# Sheet1.net
KiCad netlist of a schematic drawn in Altium Designer
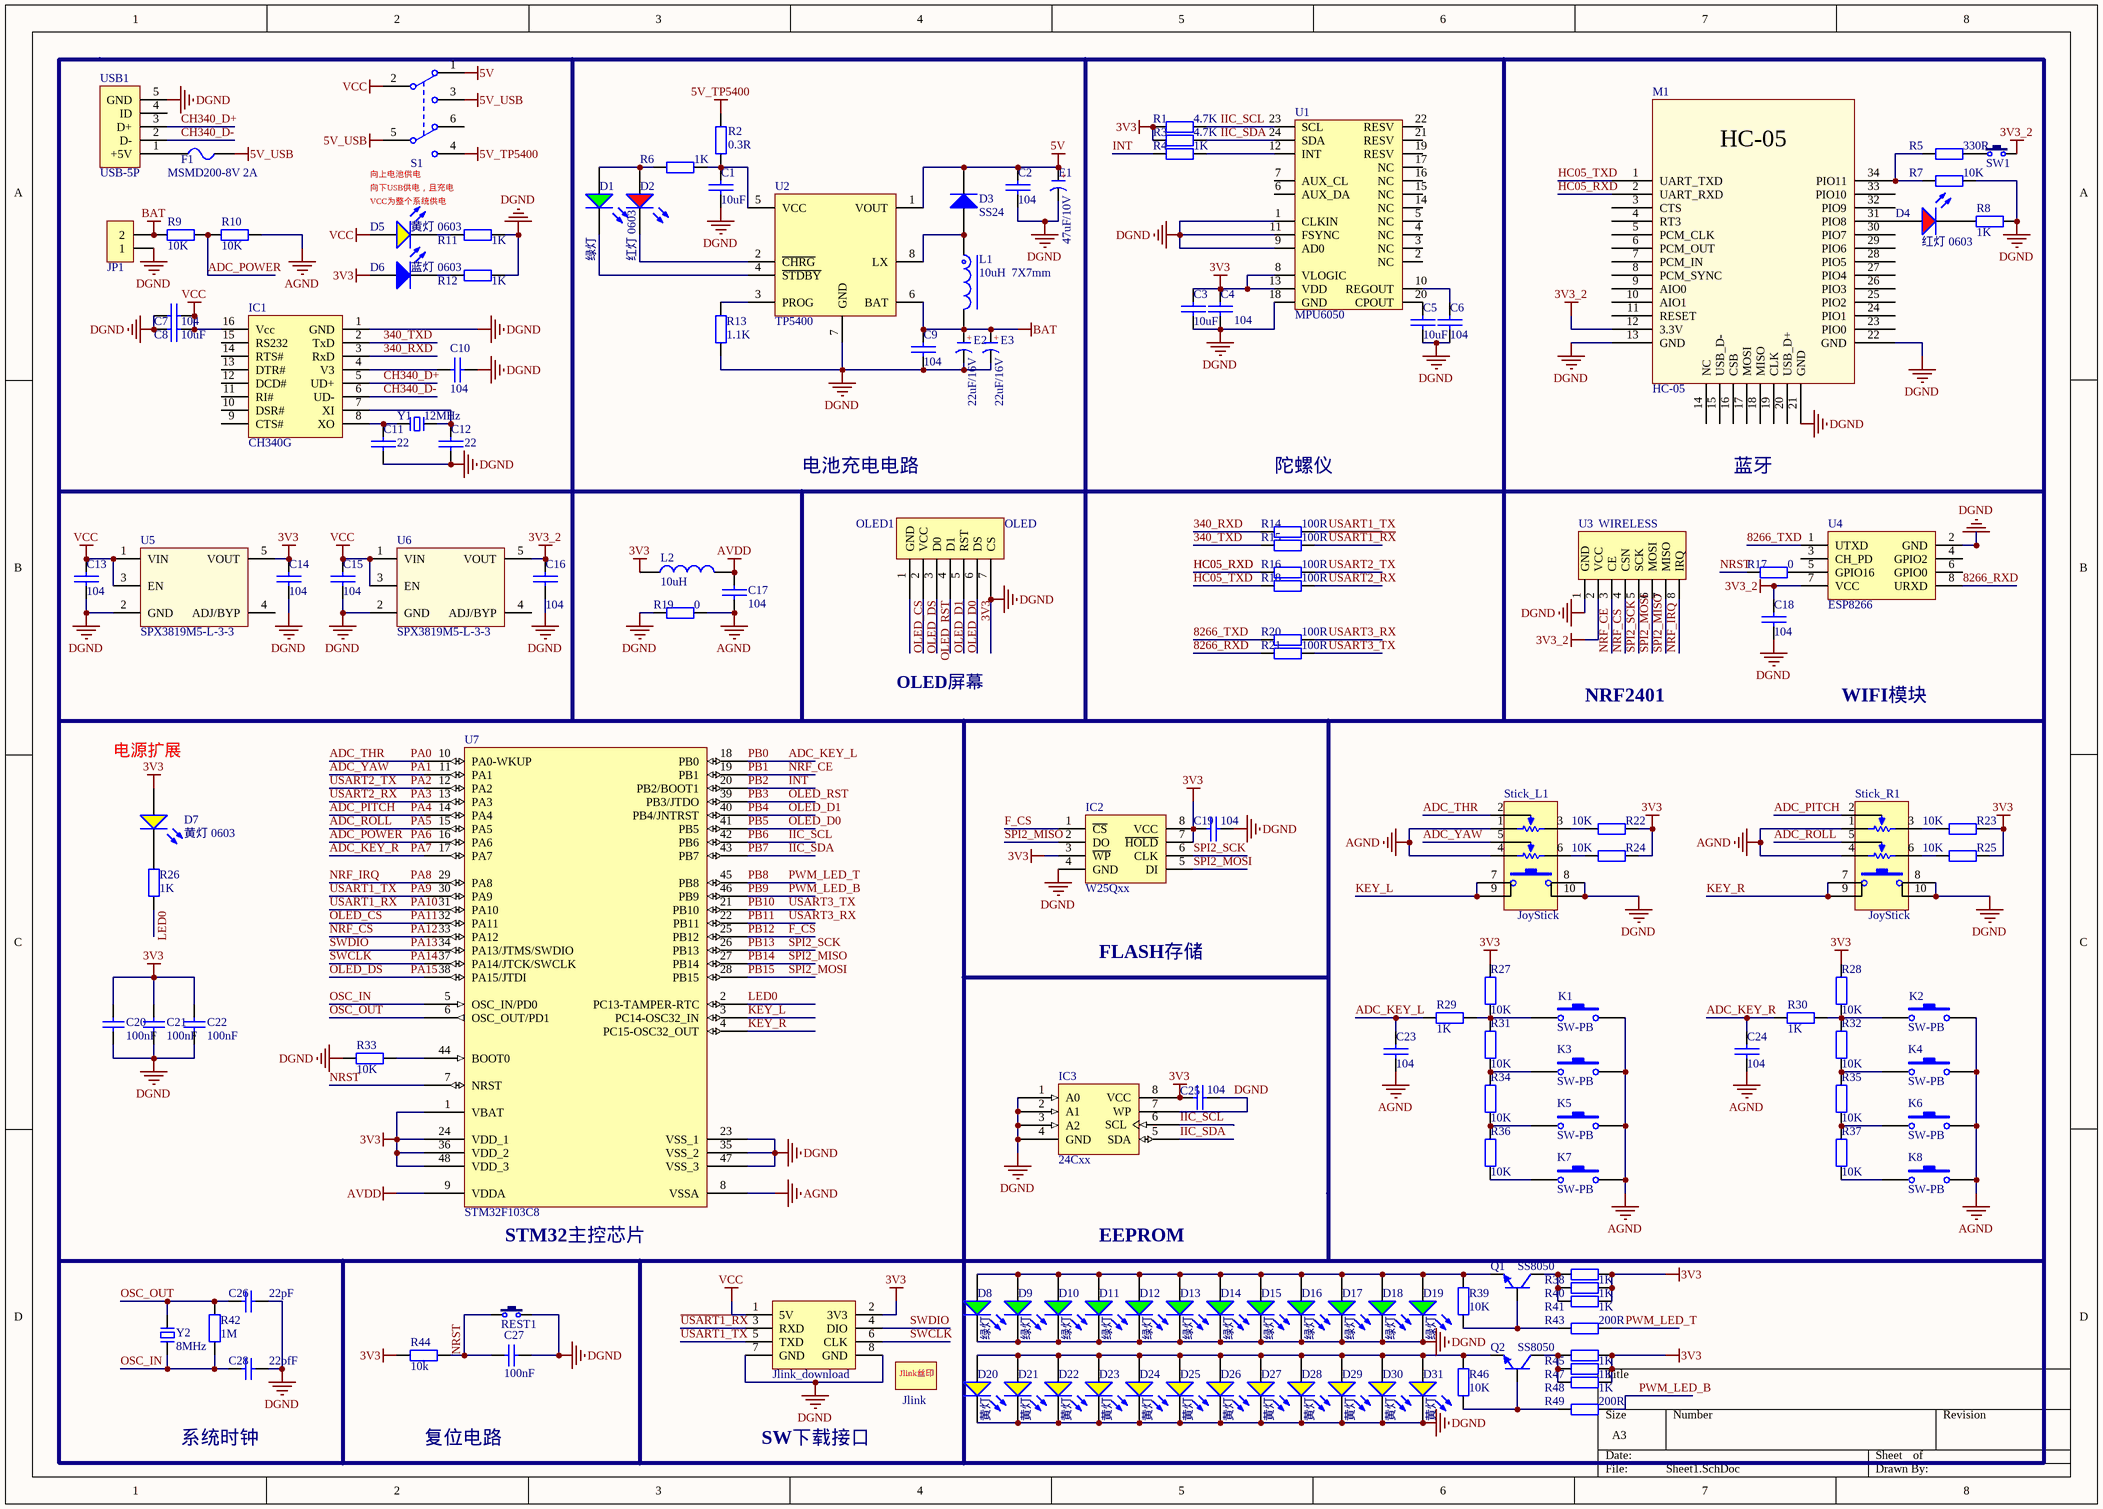
[diagram p0: Sheet1.SchDoc]

(export (version "E")
  (design (tool "Eeschema 10.0.6"))
  (components
    (comp (ref "*1")
      (value "Jlink_download")
      (footprint "HDR2.54-M-LI-2x4P")
      (description "Jlink下载器")
      (libsource (lib "15.1 - 未分类器件") (part "Jlink_下载器"))
    )
    (comp (ref "*2")
      (value "Jlink")
      (footprint "Jlink_Load")
      (description "Jlink丝印")
      (libsource (lib "15.1 - 未分类器件") (part "Jlink"))
    )
    (comp (ref "C1")
      (value "10uF")
      (footprint "LC-0805_C")
      (description "Capacitor 0805")
      (libsource (lib "CD's_LIB_2018") (part "0805C"))
    )
    (comp (ref "C2")
      (value "104")
      (footprint "LC-0603_C")
      (description "Capacitor 0805")
      (libsource (lib "CD's_LIB_2018") (part "0805C"))
    )
    (comp (ref "C3")
      (value "10uF")
      (footprint "LC-0805_C")
      (description "Capacitor 0805")
      (libsource (lib "CD's_LIB_2018") (part "0805C"))
    )
    (comp (ref "C4")
      (value "104")
      (footprint "LC-0603_C")
      (description "Capacitor 0805")
      (libsource (lib "CD's_LIB_2018") (part "0805C"))
    )
    (comp (ref "C5")
      (value "10uF")
      (footprint "LC-0805_C")
      (description "Capacitor 0805")
      (libsource (lib "CD's_LIB_2018") (part "0805C"))
    )
    (comp (ref "C6")
      (value "104")
      (footprint "LC-0603_C")
      (description "Capacitor 0805")
      (libsource (lib "CD's_LIB_2018") (part "0805C"))
    )
    (comp (ref "C7")
      (value "104")
      (footprint "LC-0603_C")
      (description "Capacitor 0805")
      (libsource (lib "CD's_LIB_2018") (part "0805C"))
    )
    (comp (ref "C8")
      (value "10uF")
      (footprint "LC-0805_C")
      (description "Capacitor 0805")
      (libsource (lib "CD's_LIB_2018") (part "0805C"))
    )
    (comp (ref "C9")
      (value "104")
      (footprint "LC-0603_C")
      (description "Capacitor 0805")
      (libsource (lib "CD's_LIB_2018") (part "0805C"))
    )
    (comp (ref "C10")
      (value "104")
      (footprint "LC-0603_C")
      (description "Capacitor 0805")
      (libsource (lib "CD's_LIB_2018") (part "0805C"))
    )
    (comp (ref "C11")
      (value "22")
      (footprint "LC-0603_C")
      (description "Capacitor 0805")
      (libsource (lib "CD's_LIB_2018") (part "0805C"))
    )
    (comp (ref "C12")
      (value "22")
      (footprint "LC-0603_C")
      (description "Capacitor 0805")
      (libsource (lib "CD's_LIB_2018") (part "0805C"))
    )
    (comp (ref "C13")
      (value "104")
      (footprint "LC-0603_C")
      (description "Capacitor 0805")
      (libsource (lib "CD's_LIB_2018") (part "0805C"))
    )
    (comp (ref "C14")
      (value "104")
      (footprint "LC-0603_C")
      (description "Capacitor 0805")
      (libsource (lib "CD's_LIB_2018") (part "0805C"))
    )
    (comp (ref "C15")
      (value "104")
      (footprint "LC-0603_C")
      (description "Capacitor 0805")
      (libsource (lib "CD's_LIB_2018") (part "0805C"))
    )
    (comp (ref "C16")
      (value "104")
      (footprint "LC-0603_C")
      (description "Capacitor 0805")
      (libsource (lib "CD's_LIB_2018") (part "0805C"))
    )
    (comp (ref "C17")
      (value "104")
      (footprint "LC-0603_C")
      (description "Capacitor 0805")
      (libsource (lib "CD's_LIB_2018") (part "0805C"))
    )
    (comp (ref "C18")
      (value "104")
      (footprint "LC-0603_C")
      (description "Capacitor 0805")
      (libsource (lib "CD's_LIB_2018") (part "0805C"))
    )
    (comp (ref "C19")
      (value "104")
      (footprint "LC-0603_C")
      (description "Capacitor 0805")
      (libsource (lib "CD's_LIB_2018") (part "0805C"))
    )
    (comp (ref "C20")
      (value "100nF")
      (footprint "LC-0603_C")
      (description "无极性电容")
      (fields (field (name "PUBLISHER") "Altium Limited"))
      (libsource (lib "liu_2016") (part "Cap"))
    )
    (comp (ref "C21")
      (value "100nF")
      (footprint "LC-0603_C")
      (description "无极性电容")
      (fields (field (name "PUBLISHER") "Altium Limited"))
      (libsource (lib "liu_2016") (part "Cap"))
    )
    (comp (ref "C22")
      (value "100nF")
      (footprint "LC-0603_C")
      (description "无极性电容")
      (fields (field (name "PUBLISHER") "Altium Limited"))
      (libsource (lib "liu_2016") (part "Cap"))
    )
    (comp (ref "C23")
      (value "104")
      (footprint "LC-0603_C")
      (description "Capacitor 0805")
      (libsource (lib "CD's_LIB_2018") (part "0805C"))
    )
    (comp (ref "C24")
      (value "104")
      (footprint "LC-0603_C")
      (description "Capacitor 0805")
      (libsource (lib "CD's_LIB_2018") (part "0805C"))
    )
    (comp (ref "C25")
      (value "104")
      (footprint "LC-0603_C")
      (description "Capacitor 0805")
      (libsource (lib "CD's_LIB_2018") (part "0805C"))
    )
    (comp (ref "C26")
      (value "22pF")
      (footprint "LC-0603_C")
      (description "无极性电容")
      (fields (field (name "PUBLISHER") "Altium Limited"))
      (libsource (lib "liu_2016") (part "Cap"))
    )
    (comp (ref "C27")
      (value "100nF")
      (footprint "LC-0603_C")
      (description "无极性电容")
      (fields (field (name "PUBLISHER") "Altium Limited"))
      (libsource (lib "liu_2016") (part "Cap"))
    )
    (comp (ref "C28")
      (value "22pfF")
      (footprint "LC-0603_C")
      (description "无极性电容")
      (fields (field (name "PUBLISHER") "Altium Limited"))
      (libsource (lib "liu_2016") (part "Cap"))
    )
    (comp (ref "D1")
      (value "绿灯")
      (footprint "LC-0603_LED_S1")
      (description "发光二极管")
      (libsource (lib "Miscellaneous Devices LC") (part "绿灯"))
    )
    (comp (ref "D2")
      (value "红灯 0603")
      (footprint "LC-0603_LED_S1")
      (description "发光二极管")
      (libsource (lib "Miscellaneous Devices LC") (part "0603 红灯"))
    )
    (comp (ref "D3")
      (value "SS24")
      (footprint "SMB")
      (description "High Conductance Fast Diode")
      (fields (field (name "PUBLISHER") "Altium Limited"))
      (libsource (lib "Miscellaneous Devices") (part "Diode 1N4148"))
    )
    (comp (ref "D4")
      (value "红灯 0603")
      (footprint "LC-0603_LED_S1")
      (description "发光二极管")
      (libsource (lib "Miscellaneous Devices LC") (part "0603 红灯"))
    )
    (comp (ref "D5")
      (value "黄灯 0603")
      (footprint "LC-0603_LED_S1")
      (description "发光二极管")
      (libsource (lib "Miscellaneous Devices LC") (part "0603 黄灯"))
    )
    (comp (ref "D6")
      (value "蓝灯 0603")
      (footprint "LC-0603_LED_S1")
      (description "发光二极管")
      (libsource (lib "Miscellaneous Devices LC") (part "0603 蓝灯"))
    )
    (comp (ref "D7")
      (value "黄灯 0603")
      (footprint "LC-0603_LED_S1")
      (description "发光二极管")
      (libsource (lib "Miscellaneous Devices LC") (part "0603 黄灯"))
    )
    (comp (ref "D8")
      (value "绿灯")
      (footprint "LC-0603_LED_S1")
      (description "发光二极管")
      (libsource (lib "Miscellaneous Devices LC") (part "绿灯"))
    )
    (comp (ref "D9")
      (value "绿灯")
      (footprint "LC-0603_LED_S1")
      (description "发光二极管")
      (libsource (lib "Miscellaneous Devices LC") (part "绿灯"))
    )
    (comp (ref "D10")
      (value "绿灯")
      (footprint "LC-0603_LED_S1")
      (description "发光二极管")
      (libsource (lib "Miscellaneous Devices LC") (part "绿灯"))
    )
    (comp (ref "D11")
      (value "绿灯")
      (footprint "LC-0603_LED_S1")
      (description "发光二极管")
      (libsource (lib "Miscellaneous Devices LC") (part "绿灯"))
    )
    (comp (ref "D12")
      (value "绿灯")
      (footprint "LC-0603_LED_S1")
      (description "发光二极管")
      (libsource (lib "Miscellaneous Devices LC") (part "绿灯"))
    )
    (comp (ref "D13")
      (value "绿灯")
      (footprint "LC-0603_LED_S1")
      (description "发光二极管")
      (libsource (lib "Miscellaneous Devices LC") (part "绿灯"))
    )
    (comp (ref "D14")
      (value "绿灯")
      (footprint "LC-0603_LED_S1")
      (description "发光二极管")
      (libsource (lib "Miscellaneous Devices LC") (part "绿灯"))
    )
    (comp (ref "D15")
      (value "绿灯")
      (footprint "LC-0603_LED_S1")
      (description "发光二极管")
      (libsource (lib "Miscellaneous Devices LC") (part "绿灯"))
    )
    (comp (ref "D16")
      (value "绿灯")
      (footprint "LC-0603_LED_S1")
      (description "发光二极管")
      (libsource (lib "Miscellaneous Devices LC") (part "绿灯"))
    )
    (comp (ref "D17")
      (value "绿灯")
      (footprint "LC-0603_LED_S1")
      (description "发光二极管")
      (libsource (lib "Miscellaneous Devices LC") (part "绿灯"))
    )
    (comp (ref "D18")
      (value "绿灯")
      (footprint "LC-0603_LED_S1")
      (description "发光二极管")
      (libsource (lib "Miscellaneous Devices LC") (part "绿灯"))
    )
    (comp (ref "D19")
      (value "绿灯")
      (footprint "LC-0603_LED_S1")
      (description "发光二极管")
      (libsource (lib "Miscellaneous Devices LC") (part "绿灯"))
    )
    (comp (ref "D20")
      (value "黄灯")
      (footprint "LC-0603_LED_S1")
      (description "发光二极管")
      (libsource (lib "Miscellaneous Devices LC") (part "0603 黄灯"))
    )
    (comp (ref "D21")
      (value "黄灯")
      (footprint "LC-0603_LED_S1")
      (description "发光二极管")
      (libsource (lib "Miscellaneous Devices LC") (part "0603 黄灯"))
    )
    (comp (ref "D22")
      (value "黄灯")
      (footprint "LC-0603_LED_S1")
      (description "发光二极管")
      (libsource (lib "Miscellaneous Devices LC") (part "0603 黄灯"))
    )
    (comp (ref "D23")
      (value "黄灯")
      (footprint "LC-0603_LED_S1")
      (description "发光二极管")
      (libsource (lib "Miscellaneous Devices LC") (part "0603 黄灯"))
    )
    (comp (ref "D24")
      (value "黄灯")
      (footprint "LC-0603_LED_S1")
      (description "发光二极管")
      (libsource (lib "Miscellaneous Devices LC") (part "0603 黄灯"))
    )
    (comp (ref "D25")
      (value "黄灯")
      (footprint "LC-0603_LED_S1")
      (description "发光二极管")
      (libsource (lib "Miscellaneous Devices LC") (part "0603 黄灯"))
    )
    (comp (ref "D26")
      (value "黄灯")
      (footprint "LC-0603_LED_S1")
      (description "发光二极管")
      (libsource (lib "Miscellaneous Devices LC") (part "0603 黄灯"))
    )
    (comp (ref "D27")
      (value "黄灯")
      (footprint "LC-0603_LED_S1")
      (description "发光二极管")
      (libsource (lib "Miscellaneous Devices LC") (part "0603 黄灯"))
    )
    (comp (ref "D28")
      (value "黄灯")
      (footprint "LC-0603_LED_S1")
      (description "发光二极管")
      (libsource (lib "Miscellaneous Devices LC") (part "0603 黄灯"))
    )
    (comp (ref "D29")
      (value "黄灯")
      (footprint "LC-0603_LED_S1")
      (description "发光二极管")
      (libsource (lib "Miscellaneous Devices LC") (part "0603 黄灯"))
    )
    (comp (ref "D30")
      (value "黄灯")
      (footprint "LC-0603_LED_S1")
      (description "发光二极管")
      (libsource (lib "Miscellaneous Devices LC") (part "0603 黄灯"))
    )
    (comp (ref "D31")
      (value "黄灯")
      (footprint "LC-0603_LED_S1")
      (description "发光二极管")
      (libsource (lib "Miscellaneous Devices LC") (part "0603 黄灯"))
    )
    (comp (ref "E1")
      (value "47uF/10V")
      (footprint "CD B(3528)")
      (description "贴片钽电容")
      (fields (field (name "版权归属") "源创客"))
      (libsource (lib "3.1   - 电阻-电容-电感") (part "C-CD"))
    )
    (comp (ref "E2")
      (value "22uF/16V")
      (footprint "CD B(3528)")
      (description "贴片钽电容")
      (fields (field (name "版权归属") "源创客"))
      (libsource (lib "3.1   - 电阻-电容-电感") (part "C-CD"))
    )
    (comp (ref "E3")
      (value "22uF/16V")
      (footprint "CD B(3528)")
      (description "贴片钽电容")
      (fields (field (name "版权归属") "源创客"))
      (libsource (lib "3.1   - 电阻-电容-电感") (part "C-CD"))
    )
    (comp (ref "F1")
      (value "MSMD200-8V 2A")
      (footprint "FU 0805")
      (description "贴片保险丝")
      (fields (field (name "版权归属") "源创客"))
      (libsource (lib "10.1 - 保险丝-晶振") (part "FU"))
    )
    (comp (ref "IC1")
      (value "CH340G")
      (footprint "SOP16_M")
      (description "串口转USB")
      (fields (field (name "版权归属") "源创客"))
      (libsource (lib "1.1   - IC芯片") (part "CH340G"))
    )
    (comp (ref "IC2")
      (value "W25Qxx")
      (footprint "SOP8W_M")
      (description "外置Flash")
      (fields (field (name "版权归属") "源创客"))
      (libsource (lib "1.1   - IC芯片") (part "W25Qxx"))
    )
    (comp (ref "IC3")
      (value "24Cxx")
      (footprint "SOP8_M")
      (description "外置EEPROM")
      (fields (field (name "版权归属") "源创客"))
      (libsource (lib "1.1   - IC芯片") (part "24Cxx"))
    )
    (comp (ref "JP1")
      (value "HDR-1X2")
      (footprint "XH2.54-WI-2P")
      (description "2P接插件")
      (fields (field (name "版权归属") "源创客"))
      (libsource (lib "4.5   - 接插件-脚距2.54") (part "Header 2"))
    )
    (comp (ref "K1")
      (value "SW-PB")
      (footprint "TSW DIP-6*6*5")
      (description "Switch")
      (fields (field (name "PUBLISHER") "Altium Limited"))
      (libsource (lib "PCB_Project") (part "SW-PB"))
    )
    (comp (ref "K2")
      (value "SW-PB")
      (footprint "TSW DIP-6*6*5")
      (description "Switch")
      (fields (field (name "PUBLISHER") "Altium Limited"))
      (libsource (lib "PCB_Project") (part "SW-PB"))
    )
    (comp (ref "K3")
      (value "SW-PB")
      (footprint "TSW DIP-6*6*5")
      (description "Switch")
      (fields (field (name "PUBLISHER") "Altium Limited"))
      (libsource (lib "PCB_Project") (part "SW-PB"))
    )
    (comp (ref "K4")
      (value "SW-PB")
      (footprint "TSW DIP-6*6*5")
      (description "Switch")
      (fields (field (name "PUBLISHER") "Altium Limited"))
      (libsource (lib "PCB_Project") (part "SW-PB"))
    )
    (comp (ref "K5")
      (value "SW-PB")
      (footprint "TSW DIP-6*6*5")
      (description "Switch")
      (fields (field (name "PUBLISHER") "Altium Limited"))
      (libsource (lib "PCB_Project") (part "SW-PB"))
    )
    (comp (ref "K6")
      (value "SW-PB")
      (footprint "TSW DIP-6*6*5")
      (description "Switch")
      (fields (field (name "PUBLISHER") "Altium Limited"))
      (libsource (lib "PCB_Project") (part "SW-PB"))
    )
    (comp (ref "K7")
      (value "SW-PB")
      (footprint "TSW DIP-6*6*5")
      (description "Switch")
      (fields (field (name "PUBLISHER") "Altium Limited"))
      (libsource (lib "PCB_Project") (part "SW-PB"))
    )
    (comp (ref "K8")
      (value "SW-PB")
      (footprint "TSW DIP-6*6*5")
      (description "Switch")
      (fields (field (name "PUBLISHER") "Altium Limited"))
      (libsource (lib "PCB_Project") (part "SW-PB"))
    )
    (comp (ref "L1")
      (value "10uH  7X7mm")
      (footprint "CD75")
      (description "贴片功率电感")
      (fields (field (name "版权归属") "源创客"))
      (libsource (lib "3.1   - 电阻-电容-电感") (part "L-CD"))
    )
    (comp (ref "L2")
      (value "10uH")
      (footprint "L 0603")
      (description "小功率贴片电感")
      (fields (field (name "版权归属") "源创客"))
      (libsource (lib "3.1   - 电阻-电容-电感") (part "L"))
    )
    (comp (ref "M1")
      (value "HC-05")
      (footprint "HC-05")
      (description "串口蓝牙模块")
      (fields (field (name "版权归属") "源创客"))
      (libsource (lib "13.1 - 模块") (part "HC-05"))
    )
    (comp (ref "OLED1")
      (value "OLED")
      (footprint "OLED_096")
      (description "OLED屏幕")
      (libsource (lib "liu_2016") (part "OLED_SPI"))
    )
    (comp (ref "Q1")
      (value "SS8050")
      (footprint "SOT23-3L")
      (description "高频放大-NPN型")
      (fields (field (name "版权归属") "源创客"))
      (libsource (lib "6.2   - 三极管") (part "8050-SMD"))
    )
    (comp (ref "Q2")
      (value "SS8050")
      (footprint "SOT23-3L")
      (description "高频放大-NPN型")
      (fields (field (name "版权归属") "源创客"))
      (libsource (lib "6.2   - 三极管") (part "8050-SMD"))
    )
    (comp (ref "R1")
      (value "4.7K")
      (footprint "LC-0603_R")
      (description "贴片电阻")
      (fields (field (name "PUBLISHER") "Altium Limited"))
      (libsource (lib "liu_2016") (part "Res1"))
    )
    (comp (ref "R2")
      (value "0.3R")
      (footprint "R 2010_M")
      (description "贴片电阻")
      (fields (field (name "版权归属") "源创客"))
      (libsource (lib "3.1   - 电阻-电容-电感") (part "R"))
    )
    (comp (ref "R3")
      (value "4.7K")
      (footprint "LC-0603_R")
      (description "贴片电阻")
      (fields (field (name "PUBLISHER") "Altium Limited"))
      (libsource (lib "liu_2016") (part "Res1"))
    )
    (comp (ref "R4")
      (value "1K")
      (footprint "LC-0603_R")
      (description "贴片电阻")
      (fields (field (name "PUBLISHER") "Altium Limited"))
      (libsource (lib "liu_2016") (part "Res1"))
    )
    (comp (ref "R5")
      (value "330R")
      (footprint "LC-0603_R")
      (description "贴片电阻")
      (fields (field (name "PUBLISHER") "Altium Limited"))
      (libsource (lib "") (part "Res1_2"))
    )
    (comp (ref "R6")
      (value "1K")
      (footprint "LC-0603_R")
      (description "贴片电阻")
      (fields (field (name "PUBLISHER") "Altium Limited"))
      (libsource (lib "liu_2016") (part "Res1"))
    )
    (comp (ref "R7")
      (value "10K")
      (footprint "LC-0603_R")
      (description "贴片电阻")
      (fields (field (name "PUBLISHER") "Altium Limited"))
      (libsource (lib "") (part "Res1_2"))
    )
    (comp (ref "R8")
      (value "1K")
      (footprint "LC-0603_R")
      (description "贴片电阻")
      (fields (field (name "PUBLISHER") "Altium Limited"))
      (libsource (lib "") (part "Res1_2"))
    )
    (comp (ref "R9")
      (value "10K")
      (footprint "LC-0603_R")
      (description "贴片电阻")
      (fields (field (name "PUBLISHER") "Altium Limited"))
      (libsource (lib "liu_2016") (part "Res1"))
    )
    (comp (ref "R10")
      (value "10K")
      (footprint "LC-0603_R")
      (description "贴片电阻")
      (fields (field (name "PUBLISHER") "Altium Limited"))
      (libsource (lib "liu_2016") (part "Res1"))
    )
    (comp (ref "R11")
      (value "1K")
      (footprint "LC-0603_R")
      (description "贴片电阻")
      (fields (field (name "PUBLISHER") "Altium Limited"))
      (libsource (lib "liu_2016") (part "Res1"))
    )
    (comp (ref "R12")
      (value "1K")
      (footprint "LC-0603_R")
      (description "贴片电阻")
      (fields (field (name "PUBLISHER") "Altium Limited"))
      (libsource (lib "liu_2016") (part "Res1"))
    )
    (comp (ref "R13")
      (value "1.1K")
      (footprint "LC-0603_R")
      (description "贴片电阻")
      (fields (field (name "PUBLISHER") "Altium Limited"))
      (libsource (lib "") (part "Res1_1"))
    )
    (comp (ref "R14")
      (value "100R")
      (footprint "LC-0603_R")
      (description "贴片电阻")
      (fields (field (name "PUBLISHER") "Altium Limited"))
      (libsource (lib "liu_2016") (part "Res1"))
    )
    (comp (ref "R15")
      (value "100R")
      (footprint "LC-0603_R")
      (description "贴片电阻")
      (fields (field (name "PUBLISHER") "Altium Limited"))
      (libsource (lib "liu_2016") (part "Res1"))
    )
    (comp (ref "R16")
      (value "100R")
      (footprint "LC-0603_R")
      (description "贴片电阻")
      (fields (field (name "PUBLISHER") "Altium Limited"))
      (libsource (lib "liu_2016") (part "Res1"))
    )
    (comp (ref "R17")
      (value "0")
      (footprint "LC-0603_R")
      (description "贴片电阻")
      (fields (field (name "PUBLISHER") "Altium Limited"))
      (libsource (lib "liu_2016") (part "Res1"))
    )
    (comp (ref "R18")
      (value "100R")
      (footprint "LC-0603_R")
      (description "贴片电阻")
      (fields (field (name "PUBLISHER") "Altium Limited"))
      (libsource (lib "liu_2016") (part "Res1"))
    )
    (comp (ref "R19")
      (value "0")
      (footprint "LC-0603_R")
      (description "贴片电阻")
      (fields (field (name "PUBLISHER") "Altium Limited"))
      (libsource (lib "liu_2016") (part "Res1"))
    )
    (comp (ref "R20")
      (value "100R")
      (footprint "LC-0603_R")
      (description "贴片电阻")
      (fields (field (name "PUBLISHER") "Altium Limited"))
      (libsource (lib "liu_2016") (part "Res1"))
    )
    (comp (ref "R21")
      (value "100R")
      (footprint "LC-0603_R")
      (description "贴片电阻")
      (fields (field (name "PUBLISHER") "Altium Limited"))
      (libsource (lib "liu_2016") (part "Res1"))
    )
    (comp (ref "R22")
      (value "10K")
      (footprint "LC-0603_R")
      (description "贴片电阻")
      (fields (field (name "PUBLISHER") "Altium Limited"))
      (libsource (lib "") (part "Res1_2"))
    )
    (comp (ref "R23")
      (value "10K")
      (footprint "LC-0603_R")
      (description "贴片电阻")
      (fields (field (name "PUBLISHER") "Altium Limited"))
      (libsource (lib "") (part "Res1_2"))
    )
    (comp (ref "R24")
      (value "10K")
      (footprint "LC-0603_R")
      (description "贴片电阻")
      (fields (field (name "PUBLISHER") "Altium Limited"))
      (libsource (lib "") (part "Res1_2"))
    )
    (comp (ref "R25")
      (value "10K")
      (footprint "LC-0603_R")
      (description "贴片电阻")
      (fields (field (name "PUBLISHER") "Altium Limited"))
      (libsource (lib "") (part "Res1_2"))
    )
    (comp (ref "R26")
      (value "1K")
      (footprint "LC-0603_R")
      (description "贴片电阻")
      (fields (field (name "PUBLISHER") "Altium Limited"))
      (libsource (lib "") (part "Res1_1"))
    )
    (comp (ref "R27")
      (value "10K")
      (footprint "LC-0603_R")
      (description "贴片电阻")
      (fields (field (name "PUBLISHER") "Altium Limited"))
      (libsource (lib "") (part "Res1_1"))
    )
    (comp (ref "R28")
      (value "10K")
      (footprint "LC-0603_R")
      (description "贴片电阻")
      (fields (field (name "PUBLISHER") "Altium Limited"))
      (libsource (lib "") (part "Res1_1"))
    )
    (comp (ref "R29")
      (value "1K")
      (footprint "LC-0603_R")
      (description "贴片电阻")
      (fields (field (name "PUBLISHER") "Altium Limited"))
      (libsource (lib "") (part "Res1_2"))
    )
    (comp (ref "R30")
      (value "1K")
      (footprint "LC-0603_R")
      (description "贴片电阻")
      (fields (field (name "PUBLISHER") "Altium Limited"))
      (libsource (lib "") (part "Res1_2"))
    )
    (comp (ref "R31")
      (value "10K")
      (footprint "LC-0603_R")
      (description "贴片电阻")
      (fields (field (name "PUBLISHER") "Altium Limited"))
      (libsource (lib "") (part "Res1_1"))
    )
    (comp (ref "R32")
      (value "10K")
      (footprint "LC-0603_R")
      (description "贴片电阻")
      (fields (field (name "PUBLISHER") "Altium Limited"))
      (libsource (lib "") (part "Res1_1"))
    )
    (comp (ref "R33")
      (value "10K")
      (footprint "LC-0603_R")
      (description "贴片电阻")
      (fields (field (name "PUBLISHER") "Altium Limited"))
      (libsource (lib "liu_2016") (part "Res1"))
    )
    (comp (ref "R34")
      (value "10K")
      (footprint "LC-0603_R")
      (description "贴片电阻")
      (fields (field (name "PUBLISHER") "Altium Limited"))
      (libsource (lib "") (part "Res1_1"))
    )
    (comp (ref "R35")
      (value "10K")
      (footprint "LC-0603_R")
      (description "贴片电阻")
      (fields (field (name "PUBLISHER") "Altium Limited"))
      (libsource (lib "") (part "Res1_1"))
    )
    (comp (ref "R36")
      (value "10K")
      (footprint "LC-0603_R")
      (description "贴片电阻")
      (fields (field (name "PUBLISHER") "Altium Limited"))
      (libsource (lib "") (part "Res1_1"))
    )
    (comp (ref "R37")
      (value "10K")
      (footprint "LC-0603_R")
      (description "贴片电阻")
      (fields (field (name "PUBLISHER") "Altium Limited"))
      (libsource (lib "") (part "Res1_1"))
    )
    (comp (ref "R38")
      (value "1K")
      (footprint "LC-0603_R")
      (description "贴片电阻")
      (fields (field (name "PUBLISHER") "Altium Limited"))
      (libsource (lib "liu_2016") (part "Res1"))
    )
    (comp (ref "R39")
      (value "10K")
      (footprint "LC-0603_R")
      (description "贴片电阻")
      (fields (field (name "PUBLISHER") "Altium Limited"))
      (libsource (lib "") (part "Res1_1"))
    )
    (comp (ref "R40")
      (value "1K")
      (footprint "LC-0603_R")
      (description "贴片电阻")
      (fields (field (name "PUBLISHER") "Altium Limited"))
      (libsource (lib "liu_2016") (part "Res1"))
    )
    (comp (ref "R41")
      (value "1K")
      (footprint "LC-0603_R")
      (description "贴片电阻")
      (fields (field (name "PUBLISHER") "Altium Limited"))
      (libsource (lib "liu_2016") (part "Res1"))
    )
    (comp (ref "R42")
      (value "1M")
      (footprint "LC-0603_R")
      (description "贴片电阻")
      (fields (field (name "PUBLISHER") "Altium Limited"))
      (libsource (lib "") (part "Res1_3"))
    )
    (comp (ref "R43")
      (value "200R")
      (footprint "LC-0603_R")
      (description "贴片电阻")
      (fields (field (name "PUBLISHER") "Altium Limited"))
      (libsource (lib "liu_2016") (part "Res1"))
    )
    (comp (ref "R44")
      (value "10k")
      (footprint "LC-0603_R")
      (description "贴片电阻")
      (fields (field (name "PUBLISHER") "Altium Limited"))
      (libsource (lib "") (part "Res1_2"))
    )
    (comp (ref "R45")
      (value "1K")
      (footprint "LC-0603_R")
      (description "贴片电阻")
      (fields (field (name "PUBLISHER") "Altium Limited"))
      (libsource (lib "liu_2016") (part "Res1"))
    )
    (comp (ref "R46")
      (value "10K")
      (footprint "LC-0603_R")
      (description "贴片电阻")
      (fields (field (name "PUBLISHER") "Altium Limited"))
      (libsource (lib "") (part "Res1_1"))
    )
    (comp (ref "R47")
      (value "1K")
      (footprint "LC-0603_R")
      (description "贴片电阻")
      (fields (field (name "PUBLISHER") "Altium Limited"))
      (libsource (lib "liu_2016") (part "Res1"))
    )
    (comp (ref "R48")
      (value "1K")
      (footprint "LC-0603_R")
      (description "贴片电阻")
      (fields (field (name "PUBLISHER") "Altium Limited"))
      (libsource (lib "liu_2016") (part "Res1"))
    )
    (comp (ref "R49")
      (value "200R")
      (footprint "LC-0603_R")
      (description "贴片电阻")
      (fields (field (name "PUBLISHER") "Altium Limited"))
      (libsource (lib "liu_2016") (part "Res1"))
    )
    (comp (ref "REST1")
      (value "3x6x5")
      (footprint "TSW SMD-3*6*2.5")
      (description "3x6轻触开关")
      (fields (field (name "版权归属") "源创客"))
      (libsource (lib "5.1   - 按键-开关") (part "TSW 3x6"))
    )
    (comp (ref "S1")
      (value "SK-22D02")
      (footprint "SS-22H07-G2")
      (description "2路波动开关")
      (fields (field (name "版权归属") "源创客"))
      (libsource (lib "5.1   - 按键-开关") (part "SSW-2P"))
    )
    (comp (ref "Stick_L1")
      (value "JoyStick")
      (footprint "Stick")
      (description "模拟摇杆")
      (libsource (lib "Fszhang") (part "JoyStick"))
    )
    (comp (ref "Stick_R1")
      (value "JoyStick")
      (footprint "Stick")
      (description "模拟摇杆")
      (libsource (lib "Fszhang") (part "JoyStick"))
    )
    (comp (ref "SW1")
      (value "3x6x5")
      (footprint "TSW SMD-3*6*2.5")
      (description "3x6轻触开关")
      (fields (field (name "版权归属") "源创客"))
      (libsource (lib "5.1   - 按键-开关") (part "TSW 3x6"))
    )
    (comp (ref "U1")
      (value "MPU6050")
      (footprint "QFN24 4x4_M")
      (description "9轴运动处理传感器")
      (libsource (lib "Explorer STM32F407封装库") (part "MPU6050"))
    )
    (comp (ref "U2")
      (value "TP5400")
      (footprint "SOP8_M")
      (description "锂电池充电芯片")
      (libsource (lib "1.3   - 电源类芯片") (part "TP5400"))
    )
    (comp (ref "U3")
      (value "WIRELESS")
      (footprint "2*4HEADER")
      (libsource (lib "SWUST_PanPan") (part "NRF24L01"))
    )
    (comp (ref "U4")
      (value "ESP8266")
      (footprint "2*4HEADER")
      (description "WIFI通信模块")
      (libsource (lib "13.1 - 模块") (part "ESP8266"))
    )
    (comp (ref "U5")
      (value "SPX3819M5-L-3-3")
      (footprint "SOT23-5M")
      (libsource (lib "SWUST_PanPan") (part "SPX3819M5-L-3-3"))
    )
    (comp (ref "U6")
      (value "SPX3819M5-L-3-3")
      (footprint "SOT23-5M")
      (libsource (lib "SWUST_PanPan") (part "SPX3819M5-L-3-3"))
    )
    (comp (ref "U7")
      (value "STM32F103C8")
      (footprint "LQFP48 7X7_M")
      (description "Flaah:64/RAM:20/IO:36")
      (fields (field (name "版权归属") "源创客"))
      (libsource (lib "2.1   - STM32系列单片机") (part "STM32F103C8"))
    )
    (comp (ref "USB1")
      (value "USB-5P")
      (footprint "USB-MICRO_A")
      (description "微型USB母座")
      (fields (field (name "版权归属") "源创客"))
      (libsource (lib "4.1   - 接口类") (part "USB-5P"))
    )
    (comp (ref "Y1")
      (value "12MHz")
      (footprint "OSC HC-49S")
      (description "2脚无源脚晶振")
      (fields (field (name "版权归属") "源创客"))
      (libsource (lib "10.1 - 保险丝-晶振") (part "XTAL-2P"))
    )
    (comp (ref "Y2")
      (value "8MHz")
      (footprint "OSC HC-49S")
      (description "2脚无源脚晶振")
      (fields (field (name "版权归属") "源创客"))
      (libsource (lib "10.1 - 保险丝-晶振") (part "XTAL-2P"))
    )
  )
  (nets
    (net (code "1") (name "/340_RXD") (class "Default")
      (node (ref "IC1") (pin "3") (pinfunction "RxD_3") (pintype "passive"))
      (node (ref "R14") (pin "2") (pinfunction "2_2") (pintype "passive"))
    )
    (net (code "2") (name "/340_TXD") (class "Default")
      (node (ref "IC1") (pin "2") (pinfunction "TxD_2") (pintype "passive"))
      (node (ref "R15") (pin "2") (pinfunction "2_2") (pintype "passive"))
    )
    (net (code "3") (name "/8266_RXD") (class "Default")
      (node (ref "R21") (pin "2") (pinfunction "2_2") (pintype "passive"))
      (node (ref "U4") (pin "8") (pinfunction "URXD_8") (pintype "passive"))
    )
    (net (code "4") (name "/8266_TXD") (class "Default")
      (node (ref "R20") (pin "2") (pinfunction "2_2") (pintype "passive"))
      (node (ref "U4") (pin "1") (pinfunction "UTXD_1") (pintype "passive"))
    )
    (net (code "5") (name "/ADC_KEY_L") (class "Default")
      (node (ref "C23") (pin "2") (pinfunction "2_2") (pintype "passive"))
      (node (ref "R29") (pin "1") (pinfunction "1_1") (pintype "passive"))
      (node (ref "U7") (pin "18") (pinfunction "PB0_18") (pintype "bidirectional"))
    )
    (net (code "6") (name "/ADC_KEY_R") (class "Default")
      (node (ref "C24") (pin "2") (pinfunction "2_2") (pintype "passive"))
      (node (ref "R30") (pin "1") (pinfunction "1_1") (pintype "passive"))
      (node (ref "U7") (pin "17") (pinfunction "PA7_17") (pintype "bidirectional"))
    )
    (net (code "7") (name "/ADC_PITCH") (class "Default")
      (node (ref "Stick_R1") (pin "2") (pinfunction "TAP_2") (pintype "passive"))
      (node (ref "U7") (pin "14") (pinfunction "PA4_14") (pintype "bidirectional"))
    )
    (net (code "8") (name "/ADC_POWER") (class "Default")
      (node (ref "R10") (pin "2") (pinfunction "2_2") (pintype "passive"))
      (node (ref "R9") (pin "1") (pinfunction "1_1") (pintype "passive"))
      (node (ref "U7") (pin "16") (pinfunction "PA6_16") (pintype "bidirectional"))
    )
    (net (code "9") (name "/ADC_ROLL") (class "Default")
      (node (ref "Stick_R1") (pin "5") (pinfunction "TAP_5") (pintype "passive"))
      (node (ref "U7") (pin "15") (pinfunction "PA5_15") (pintype "bidirectional"))
    )
    (net (code "10") (name "/ADC_THR") (class "Default")
      (node (ref "Stick_L1") (pin "2") (pinfunction "TAP_2") (pintype "passive"))
      (node (ref "U7") (pin "10") (pinfunction "PA0-WKUP_10") (pintype "bidirectional"))
    )
    (net (code "11") (name "/ADC_YAW") (class "Default")
      (node (ref "Stick_L1") (pin "5") (pinfunction "TAP_5") (pintype "passive"))
      (node (ref "U7") (pin "11") (pinfunction "PA1_11") (pintype "bidirectional"))
    )
    (net (code "12") (name "/CH340_D+") (class "Default")
      (node (ref "IC1") (pin "5") (pinfunction "UD+_5") (pintype "passive"))
      (node (ref "USB1") (pin "3") (pinfunction "D+_3") (pintype "passive"))
    )
    (net (code "13") (name "/CH340_D-") (class "Default")
      (node (ref "IC1") (pin "6") (pinfunction "UD-_6") (pintype "passive"))
      (node (ref "USB1") (pin "2") (pinfunction "D-_2") (pintype "passive"))
    )
    (net (code "14") (name "/F_CS") (class "Default")
      (node (ref "IC2") (pin "1") (pinfunction "~{CS}_1") (pintype "passive"))
      (node (ref "U7") (pin "25") (pinfunction "PB12_25") (pintype "bidirectional"))
    )
    (net (code "15") (name "/HC05_RXD") (class "Default")
      (node (ref "M1") (pin "2") (pinfunction "UART_RXD_2") (pintype "passive"))
      (node (ref "R16") (pin "2") (pinfunction "2_2") (pintype "passive"))
    )
    (net (code "16") (name "/HC05_TXD") (class "Default")
      (node (ref "M1") (pin "1") (pinfunction "UART_TXD_1") (pintype "passive"))
      (node (ref "R18") (pin "2") (pinfunction "2_2") (pintype "passive"))
    )
    (net (code "17") (name "/IIC_SCL") (class "Default")
      (node (ref "IC3") (pin "6") (pinfunction "SCL_6") (pintype "input"))
      (node (ref "R1") (pin "1") (pinfunction "1_1") (pintype "passive"))
      (node (ref "U1") (pin "23") (pinfunction "SCL_23") (pintype "passive"))
      (node (ref "U7") (pin "42") (pinfunction "PB6_42") (pintype "bidirectional"))
    )
    (net (code "18") (name "/IIC_SDA") (class "Default")
      (node (ref "IC3") (pin "5") (pinfunction "SDA_5") (pintype "bidirectional"))
      (node (ref "R3") (pin "1") (pinfunction "1_1") (pintype "passive"))
      (node (ref "U1") (pin "24") (pinfunction "SDA_24") (pintype "passive"))
      (node (ref "U7") (pin "43") (pinfunction "PB7_43") (pintype "bidirectional"))
    )
    (net (code "19") (name "/INT") (class "Default")
      (node (ref "R4") (pin "2") (pinfunction "2_2") (pintype "passive"))
      (node (ref "U7") (pin "20") (pinfunction "PB2/BOOT1_20") (pintype "bidirectional"))
    )
    (net (code "20") (name "/KEY_L") (class "Default")
      (node (ref "Stick_L1") (pin "7") (pintype "passive"))
      (node (ref "Stick_L1") (pin "9") (pintype "passive"))
      (node (ref "U7") (pin "3") (pinfunction "PC14-OSC32_IN_3") (pintype "bidirectional"))
    )
    (net (code "21") (name "/KEY_R") (class "Default")
      (node (ref "Stick_R1") (pin "7") (pintype "passive"))
      (node (ref "Stick_R1") (pin "9") (pintype "passive"))
      (node (ref "U7") (pin "4") (pinfunction "PC15-OSC32_OUT_4") (pintype "bidirectional"))
    )
    (net (code "22") (name "/LED0") (class "Default")
      (node (ref "R26") (pin "2") (pinfunction "2_2") (pintype "passive"))
      (node (ref "U7") (pin "2") (pinfunction "PC13-TAMPER-RTC_2") (pintype "bidirectional"))
    )
    (net (code "23") (name "/NRF_CE") (class "Default")
      (node (ref "U3") (pin "3") (pinfunction "CE_3") (pintype "passive"))
      (node (ref "U7") (pin "19") (pinfunction "PB1_19") (pintype "bidirectional"))
    )
    (net (code "24") (name "/NRF_CS") (class "Default")
      (node (ref "U3") (pin "4") (pinfunction "CSN_4") (pintype "passive"))
      (node (ref "U7") (pin "33") (pinfunction "PA12_33") (pintype "bidirectional"))
    )
    (net (code "25") (name "/NRF_IRQ") (class "Default")
      (node (ref "U3") (pin "8") (pinfunction "IRQ_8") (pintype "passive"))
      (node (ref "U7") (pin "29") (pinfunction "PA8_29") (pintype "bidirectional"))
    )
    (net (code "26") (name "/NRST") (class "Default")
      (node (ref "C27") (pin "1") (pinfunction "1_1") (pintype "passive"))
      (node (ref "R17") (pin "2") (pinfunction "2_2") (pintype "passive"))
      (node (ref "R44") (pin "2") (pinfunction "2_2") (pintype "passive"))
      (node (ref "REST1") (pin "1") (pinfunction "1_1") (pintype "passive"))
      (node (ref "U7") (pin "7") (pinfunction "NRST_7") (pintype "bidirectional"))
    )
    (net (code "27") (name "/OLED_CS") (class "Default")
      (node (ref "OLED1") (pin "1") (pinfunction "GND_1") (pintype "passive"))
      (node (ref "U7") (pin "32") (pinfunction "PA11_32") (pintype "bidirectional"))
    )
    (net (code "28") (name "/OLED_D0") (class "Default")
      (node (ref "OLED1") (pin "5") (pinfunction "RST_5") (pintype "passive"))
      (node (ref "U7") (pin "41") (pinfunction "PB5_41") (pintype "bidirectional"))
    )
    (net (code "29") (name "/OLED_D1") (class "Default")
      (node (ref "OLED1") (pin "4") (pinfunction "D1_4") (pintype "passive"))
      (node (ref "U7") (pin "40") (pinfunction "PB4/JNTRST_40") (pintype "bidirectional"))
    )
    (net (code "30") (name "/OLED_DS") (class "Default")
      (node (ref "OLED1") (pin "2") (pinfunction "VCC_2") (pintype "passive"))
      (node (ref "U7") (pin "38") (pinfunction "PA15/JTDI_38") (pintype "bidirectional"))
    )
    (net (code "31") (name "/OLED_RST") (class "Default")
      (node (ref "OLED1") (pin "3") (pinfunction "D0_3") (pintype "passive"))
      (node (ref "U7") (pin "39") (pinfunction "PB3/JTDO_39") (pintype "bidirectional"))
    )
    (net (code "32") (name "/OSC_IN") (class "Default")
      (node (ref "C28") (pin "1") (pinfunction "1_1") (pintype "passive"))
      (node (ref "R42") (pin "1") (pinfunction "1_1") (pintype "passive"))
      (node (ref "U7") (pin "5") (pinfunction "OSC_IN/PD0_5") (pintype "input"))
      (node (ref "Y2") (pin "1") (pinfunction "1_1") (pintype "passive"))
    )
    (net (code "33") (name "/OSC_OUT") (class "Default")
      (node (ref "C26") (pin "1") (pinfunction "1_1") (pintype "passive"))
      (node (ref "R42") (pin "2") (pinfunction "2_2") (pintype "passive"))
      (node (ref "U7") (pin "6") (pinfunction "OSC_OUT/PD1_6") (pintype "output"))
      (node (ref "Y2") (pin "2") (pinfunction "2_2") (pintype "passive"))
    )
    (net (code "34") (name "/PA2") (class "Default")
      (node (ref "R16") (pin "1") (pinfunction "1_1") (pintype "passive"))
      (node (ref "U7") (pin "12") (pinfunction "PA2_12") (pintype "bidirectional"))
    )
    (net (code "35") (name "/PA3") (class "Default")
      (node (ref "R18") (pin "1") (pinfunction "1_1") (pintype "passive"))
      (node (ref "U7") (pin "13") (pinfunction "PA3_13") (pintype "bidirectional"))
    )
    (net (code "36") (name "/PA9") (class "Default")
      (node (ref "*1") (pin "5") (pinfunction "TXD_5") (pintype "passive"))
      (node (ref "R14") (pin "1") (pinfunction "1_1") (pintype "passive"))
      (node (ref "U7") (pin "30") (pinfunction "PA9_30") (pintype "bidirectional"))
    )
    (net (code "37") (name "/PA10") (class "Default")
      (node (ref "*1") (pin "3") (pinfunction "RXD_3") (pintype "passive"))
      (node (ref "R15") (pin "1") (pinfunction "1_1") (pintype "passive"))
      (node (ref "U7") (pin "31") (pinfunction "PA10_31") (pintype "bidirectional"))
    )
    (net (code "38") (name "/PA13") (class "Default")
      (node (ref "*1") (pin "4") (pinfunction "DIO_4") (pintype "passive"))
      (node (ref "U7") (pin "34") (pinfunction "PA13/JTMS/SWDIO_34") (pintype "bidirectional"))
    )
    (net (code "39") (name "/PA14") (class "Default")
      (node (ref "*1") (pin "6") (pinfunction "CLK_6") (pintype "passive"))
      (node (ref "U7") (pin "37") (pinfunction "PA14/JTCK/SWCLK_37") (pintype "bidirectional"))
    )
    (net (code "40") (name "/PB8") (class "Default")
      (node (ref "R43") (pin "1") (pinfunction "1_1") (pintype "passive"))
      (node (ref "U7") (pin "45") (pinfunction "PB8_45") (pintype "bidirectional"))
    )
    (net (code "41") (name "/PB9") (class "Default")
      (node (ref "R49") (pin "1") (pinfunction "1_1") (pintype "passive"))
      (node (ref "U7") (pin "46") (pinfunction "PB9_46") (pintype "bidirectional"))
    )
    (net (code "42") (name "/PB10") (class "Default")
      (node (ref "R21") (pin "1") (pinfunction "1_1") (pintype "passive"))
      (node (ref "U7") (pin "21") (pinfunction "PB10_21") (pintype "bidirectional"))
    )
    (net (code "43") (name "/PB11") (class "Default")
      (node (ref "R20") (pin "1") (pinfunction "1_1") (pintype "passive"))
      (node (ref "U7") (pin "22") (pinfunction "PB11_22") (pintype "bidirectional"))
    )
    (net (code "44") (name "/PB13") (class "Default")
      (node (ref "IC2") (pin "6") (pinfunction "CLK_6") (pintype "passive"))
      (node (ref "U3") (pin "5") (pinfunction "SCK_5") (pintype "passive"))
      (node (ref "U7") (pin "26") (pinfunction "PB13_26") (pintype "bidirectional"))
    )
    (net (code "45") (name "/PB14") (class "Default")
      (node (ref "IC2") (pin "2") (pinfunction "DO_2") (pintype "passive"))
      (node (ref "U3") (pin "7") (pinfunction "MISO_7") (pintype "passive"))
      (node (ref "U7") (pin "27") (pinfunction "PB14_27") (pintype "bidirectional"))
    )
    (net (code "46") (name "/PB15") (class "Default")
      (node (ref "IC2") (pin "5") (pinfunction "DI_5") (pintype "passive"))
      (node (ref "U3") (pin "6") (pinfunction "MOSI_6") (pintype "passive"))
      (node (ref "U7") (pin "28") (pinfunction "PB15_28") (pintype "bidirectional"))
    )
    (net (code "47") (name "3V3") (class "Default")
      (node (ref "*1") (pin "2") (pinfunction "3V3_2") (pintype "passive"))
      (node (ref "C14") (pin "2") (pinfunction "2_2") (pintype "passive"))
      (node (ref "C19") (pin "2") (pinfunction "2_2") (pintype "passive"))
      (node (ref "C20") (pin "1") (pinfunction "1_1") (pintype "passive"))
      (node (ref "C21") (pin "1") (pinfunction "1_1") (pintype "passive"))
      (node (ref "C22") (pin "1") (pinfunction "1_1") (pintype "passive"))
      (node (ref "C25") (pin "2") (pinfunction "2_2") (pintype "passive"))
      (node (ref "C3") (pin "2") (pinfunction "2_2") (pintype "passive"))
      (node (ref "C4") (pin "2") (pinfunction "2_2") (pintype "passive"))
      (node (ref "D6") (pin "A") (pinfunction "A_A") (pintype "passive"))
      (node (ref "D7") (pin "A") (pinfunction "A_A") (pintype "passive"))
      (node (ref "IC2") (pin "3") (pinfunction "~{WP}_3") (pintype "passive"))
      (node (ref "IC2") (pin "7") (pinfunction "~{HOLD}_7") (pintype "passive"))
      (node (ref "IC2") (pin "8") (pinfunction "VCC_8") (pintype "passive"))
      (node (ref "IC3") (pin "8") (pinfunction "VCC_8") (pintype "power_in"))
      (node (ref "L2") (pin "1") (pinfunction "1_1") (pintype "passive"))
      (node (ref "OLED1") (pin "6") (pinfunction "DS_6") (pintype "passive"))
      (node (ref "R1") (pin "2") (pinfunction "2_2") (pintype "passive"))
      (node (ref "R22") (pin "2") (pinfunction "2_2") (pintype "passive"))
      (node (ref "R23") (pin "2") (pinfunction "2_2") (pintype "passive"))
      (node (ref "R24") (pin "2") (pinfunction "2_2") (pintype "passive"))
      (node (ref "R25") (pin "2") (pinfunction "2_2") (pintype "passive"))
      (node (ref "R27") (pin "1") (pinfunction "1_1") (pintype "passive"))
      (node (ref "R28") (pin "1") (pinfunction "1_1") (pintype "passive"))
      (node (ref "R3") (pin "2") (pinfunction "2_2") (pintype "passive"))
      (node (ref "R38") (pin "1") (pinfunction "1_1") (pintype "passive"))
      (node (ref "R40") (pin "1") (pinfunction "1_1") (pintype "passive"))
      (node (ref "R41") (pin "1") (pinfunction "1_1") (pintype "passive"))
      (node (ref "R44") (pin "1") (pinfunction "1_1") (pintype "passive"))
      (node (ref "R45") (pin "1") (pinfunction "1_1") (pintype "passive"))
      (node (ref "R47") (pin "1") (pinfunction "1_1") (pintype "passive"))
      (node (ref "R48") (pin "1") (pinfunction "1_1") (pintype "passive"))
      (node (ref "U1") (pin "13") (pinfunction "VDD_13") (pintype "passive"))
      (node (ref "U1") (pin "8") (pinfunction "VLOGIC_8") (pintype "passive"))
      (node (ref "U5") (pin "5") (pinfunction "VOUT_5") (pintype "passive"))
      (node (ref "U7") (pin "1") (pinfunction "VBAT_1") (pintype "power_in"))
      (node (ref "U7") (pin "24") (pinfunction "VDD_1_24") (pintype "power_in"))
      (node (ref "U7") (pin "36") (pinfunction "VDD_2_36") (pintype "power_in"))
      (node (ref "U7") (pin "48") (pinfunction "VDD_3_48") (pintype "power_in"))
    )
    (net (code "48") (name "3V3_2") (class "Default")
      (node (ref "C16") (pin "2") (pinfunction "2_2") (pintype "passive"))
      (node (ref "C18") (pin "2") (pinfunction "2_2") (pintype "passive"))
      (node (ref "M1") (pin "12") (pinfunction "3.3V_12") (pintype "passive"))
      (node (ref "SW1") (pin "2") (pinfunction "2_2") (pintype "passive"))
      (node (ref "U3") (pin "2") (pinfunction "VCC_2") (pintype "passive"))
      (node (ref "U4") (pin "7") (pinfunction "VCC_7") (pintype "passive"))
      (node (ref "U6") (pin "5") (pinfunction "VOUT_5") (pintype "passive"))
    )
    (net (code "49") (name "5V") (class "Default")
      (node (ref "C2") (pin "2") (pinfunction "2_2") (pintype "passive"))
      (node (ref "D3") (pin "2") (pinfunction "K_2") (pintype "passive"))
      (node (ref "E1") (pin "1") (pinfunction "A_1") (pintype "passive"))
      (node (ref "S1") (pin "1") (pinfunction "1_1") (pintype "passive"))
      (node (ref "U2") (pin "1") (pinfunction "VOUT_1") (pintype "passive"))
    )
    (net (code "50") (name "5V_TP5400") (class "Default")
      (node (ref "R2") (pin "2") (pinfunction "2_2") (pintype "passive"))
      (node (ref "S1") (pin "4") (pinfunction "4_4") (pintype "passive"))
    )
    (net (code "51") (name "5V_USB") (class "Default")
      (node (ref "F1") (pin "2") (pinfunction "2_2") (pintype "passive"))
      (node (ref "S1") (pin "3") (pinfunction "3_3") (pintype "passive"))
      (node (ref "S1") (pin "5") (pinfunction "5_5") (pintype "passive"))
    )
    (net (code "52") (name "AGND") (class "Default")
      (node (ref "C17") (pin "1") (pinfunction "1_1") (pintype "passive"))
      (node (ref "C23") (pin "1") (pinfunction "1_1") (pintype "passive"))
      (node (ref "C24") (pin "1") (pinfunction "1_1") (pintype "passive"))
      (node (ref "K1") (pin "2") (pinfunction "2_2") (pintype "passive"))
      (node (ref "K2") (pin "2") (pinfunction "2_2") (pintype "passive"))
      (node (ref "K3") (pin "2") (pinfunction "2_2") (pintype "passive"))
      (node (ref "K4") (pin "2") (pinfunction "2_2") (pintype "passive"))
      (node (ref "K5") (pin "2") (pinfunction "2_2") (pintype "passive"))
      (node (ref "K6") (pin "2") (pinfunction "2_2") (pintype "passive"))
      (node (ref "K7") (pin "2") (pinfunction "2_2") (pintype "passive"))
      (node (ref "K8") (pin "2") (pinfunction "2_2") (pintype "passive"))
      (node (ref "R10") (pin "1") (pinfunction "1_1") (pintype "passive"))
      (node (ref "R19") (pin "1") (pinfunction "1_1") (pintype "passive"))
      (node (ref "Stick_L1") (pin "1") (pinfunction "BOT_1") (pintype "passive"))
      (node (ref "Stick_L1") (pin "4") (pinfunction "BOT_4") (pintype "passive"))
      (node (ref "Stick_R1") (pin "1") (pinfunction "BOT_1") (pintype "passive"))
      (node (ref "Stick_R1") (pin "4") (pinfunction "BOT_4") (pintype "passive"))
      (node (ref "U7") (pin "8") (pinfunction "VSSA_8") (pintype "power_in"))
    )
    (net (code "53") (name "AVDD") (class "Default")
      (node (ref "C17") (pin "2") (pinfunction "2_2") (pintype "passive"))
      (node (ref "L2") (pin "2") (pinfunction "2_2") (pintype "passive"))
      (node (ref "U7") (pin "9") (pinfunction "VDDA_9") (pintype "power_in"))
    )
    (net (code "54") (name "BAT") (class "Default")
      (node (ref "C9") (pin "2") (pinfunction "2_2") (pintype "passive"))
      (node (ref "E2") (pin "1") (pinfunction "A_1") (pintype "passive"))
      (node (ref "E3") (pin "1") (pinfunction "A_1") (pintype "passive"))
      (node (ref "JP1") (pin "2") (pinfunction "2_2") (pintype "passive"))
      (node (ref "L1") (pin "2") (pinfunction "2_2") (pintype "passive"))
      (node (ref "R9") (pin "2") (pinfunction "2_2") (pintype "passive"))
      (node (ref "U2") (pin "6") (pinfunction "BAT_6") (pintype "passive"))
    )
    (net (code "55") (name "DGND") (class "Default")
      (node (ref "*1") (pin "7") (pinfunction "GND_7") (pintype "passive"))
      (node (ref "*1") (pin "8") (pinfunction "GND_8") (pintype "passive"))
      (node (ref "C1") (pin "1") (pinfunction "1_1") (pintype "passive"))
      (node (ref "C10") (pin "1") (pinfunction "1_1") (pintype "passive"))
      (node (ref "C11") (pin "2") (pinfunction "2_2") (pintype "passive"))
      (node (ref "C12") (pin "2") (pinfunction "2_2") (pintype "passive"))
      (node (ref "C13") (pin "1") (pinfunction "1_1") (pintype "passive"))
      (node (ref "C14") (pin "1") (pinfunction "1_1") (pintype "passive"))
      (node (ref "C15") (pin "1") (pinfunction "1_1") (pintype "passive"))
      (node (ref "C16") (pin "1") (pinfunction "1_1") (pintype "passive"))
      (node (ref "C18") (pin "1") (pinfunction "1_1") (pintype "passive"))
      (node (ref "C19") (pin "1") (pinfunction "1_1") (pintype "passive"))
      (node (ref "C2") (pin "1") (pinfunction "1_1") (pintype "passive"))
      (node (ref "C20") (pin "2") (pinfunction "2_2") (pintype "passive"))
      (node (ref "C21") (pin "2") (pinfunction "2_2") (pintype "passive"))
      (node (ref "C22") (pin "2") (pinfunction "2_2") (pintype "passive"))
      (node (ref "C25") (pin "1") (pinfunction "1_1") (pintype "passive"))
      (node (ref "C26") (pin "2") (pinfunction "2_2") (pintype "passive"))
      (node (ref "C27") (pin "2") (pinfunction "2_2") (pintype "passive"))
      (node (ref "C28") (pin "2") (pinfunction "2_2") (pintype "passive"))
      (node (ref "C3") (pin "1") (pinfunction "1_1") (pintype "passive"))
      (node (ref "C4") (pin "1") (pinfunction "1_1") (pintype "passive"))
      (node (ref "C5") (pin "1") (pinfunction "1_1") (pintype "passive"))
      (node (ref "C6") (pin "2") (pinfunction "2_2") (pintype "passive"))
      (node (ref "C7") (pin "2") (pinfunction "2_2") (pintype "passive"))
      (node (ref "C8") (pin "2") (pinfunction "2_2") (pintype "passive"))
      (node (ref "C9") (pin "1") (pinfunction "1_1") (pintype "passive"))
      (node (ref "D10") (pin "K") (pinfunction "K_K") (pintype "passive"))
      (node (ref "D11") (pin "K") (pinfunction "K_K") (pintype "passive"))
      (node (ref "D12") (pin "K") (pinfunction "K_K") (pintype "passive"))
      (node (ref "D13") (pin "K") (pinfunction "K_K") (pintype "passive"))
      (node (ref "D14") (pin "K") (pinfunction "K_K") (pintype "passive"))
      (node (ref "D15") (pin "K") (pinfunction "K_K") (pintype "passive"))
      (node (ref "D16") (pin "K") (pinfunction "K_K") (pintype "passive"))
      (node (ref "D17") (pin "K") (pinfunction "K_K") (pintype "passive"))
      (node (ref "D18") (pin "K") (pinfunction "K_K") (pintype "passive"))
      (node (ref "D19") (pin "K") (pinfunction "K_K") (pintype "passive"))
      (node (ref "D20") (pin "K") (pinfunction "K_K") (pintype "passive"))
      (node (ref "D21") (pin "K") (pinfunction "K_K") (pintype "passive"))
      (node (ref "D22") (pin "K") (pinfunction "K_K") (pintype "passive"))
      (node (ref "D23") (pin "K") (pinfunction "K_K") (pintype "passive"))
      (node (ref "D24") (pin "K") (pinfunction "K_K") (pintype "passive"))
      (node (ref "D25") (pin "K") (pinfunction "K_K") (pintype "passive"))
      (node (ref "D26") (pin "K") (pinfunction "K_K") (pintype "passive"))
      (node (ref "D27") (pin "K") (pinfunction "K_K") (pintype "passive"))
      (node (ref "D28") (pin "K") (pinfunction "K_K") (pintype "passive"))
      (node (ref "D29") (pin "K") (pinfunction "K_K") (pintype "passive"))
      (node (ref "D30") (pin "K") (pinfunction "K_K") (pintype "passive"))
      (node (ref "D31") (pin "K") (pinfunction "K_K") (pintype "passive"))
      (node (ref "D8") (pin "K") (pinfunction "K_K") (pintype "passive"))
      (node (ref "D9") (pin "K") (pinfunction "K_K") (pintype "passive"))
      (node (ref "E1") (pin "2") (pinfunction "K_2") (pintype "passive"))
      (node (ref "E2") (pin "2") (pinfunction "K_2") (pintype "passive"))
      (node (ref "E3") (pin "2") (pinfunction "K_2") (pintype "passive"))
      (node (ref "IC1") (pin "1") (pinfunction "GND_1") (pintype "passive"))
      (node (ref "IC2") (pin "4") (pinfunction "GND_4") (pintype "passive"))
      (node (ref "IC3") (pin "1") (pinfunction "A0_1") (pintype "input"))
      (node (ref "IC3") (pin "2") (pinfunction "A1_2") (pintype "input"))
      (node (ref "IC3") (pin "3") (pinfunction "A2_3") (pintype "input"))
      (node (ref "IC3") (pin "4") (pinfunction "GND_4") (pintype "passive"))
      (node (ref "IC3") (pin "7") (pinfunction "WP_7") (pintype "passive"))
      (node (ref "JP1") (pin "1") (pinfunction "1_1") (pintype "passive"))
      (node (ref "M1") (pin "13") (pinfunction "GND_13") (pintype "passive"))
      (node (ref "M1") (pin "21") (pinfunction "GND_21") (pintype "passive"))
      (node (ref "M1") (pin "22") (pinfunction "GND_22") (pintype "passive"))
      (node (ref "OLED1") (pin "7") (pinfunction "CS_7") (pintype "passive"))
      (node (ref "R11") (pin "1") (pinfunction "1_1") (pintype "passive"))
      (node (ref "R12") (pin "1") (pinfunction "1_1") (pintype "passive"))
      (node (ref "R13") (pin "2") (pinfunction "2_2") (pintype "passive"))
      (node (ref "R19") (pin "2") (pinfunction "2_2") (pintype "passive"))
      (node (ref "R33") (pin "2") (pinfunction "2_2") (pintype "passive"))
      (node (ref "R7") (pin "2") (pinfunction "2_2") (pintype "passive"))
      (node (ref "R8") (pin "2") (pinfunction "2_2") (pintype "passive"))
      (node (ref "REST1") (pin "2") (pinfunction "2_2") (pintype "passive"))
      (node (ref "Stick_L1") (pin "10") (pintype "passive"))
      (node (ref "Stick_L1") (pin "8") (pintype "passive"))
      (node (ref "Stick_R1") (pin "10") (pintype "passive"))
      (node (ref "Stick_R1") (pin "8") (pintype "passive"))
      (node (ref "U1") (pin "1") (pinfunction "CLKIN_1") (pintype "passive"))
      (node (ref "U1") (pin "11") (pinfunction "FSYNC_11") (pintype "passive"))
      (node (ref "U1") (pin "18") (pinfunction "GND_18") (pintype "passive"))
      (node (ref "U1") (pin "9") (pinfunction "AD0_9") (pintype "passive"))
      (node (ref "U2") (pin "7") (pinfunction "GND_7") (pintype "passive"))
      (node (ref "U3") (pin "1") (pinfunction "GND_1") (pintype "passive"))
      (node (ref "U4") (pin "2") (pinfunction "GND_2") (pintype "passive"))
      (node (ref "U5") (pin "2") (pinfunction "GND_2") (pintype "passive"))
      (node (ref "U6") (pin "2") (pinfunction "GND_2") (pintype "passive"))
      (node (ref "U7") (pin "23") (pinfunction "VSS_1_23") (pintype "power_in"))
      (node (ref "U7") (pin "35") (pinfunction "VSS_2_35") (pintype "power_in"))
      (node (ref "U7") (pin "47") (pinfunction "VSS_3_47") (pintype "power_in"))
      (node (ref "USB1") (pin "5") (pinfunction "GND_5") (pintype "passive"))
    )
    (net (code "56") (name "Net-(D1-PadA)") (class "Default")
      (node (ref "D1") (pin "A") (pinfunction "A_A") (pintype "passive"))
      (node (ref "D2") (pin "A") (pinfunction "A_A") (pintype "passive"))
      (node (ref "R6") (pin "2") (pinfunction "2_2") (pintype "passive"))
    )
    (net (code "57") (name "Net-(D3-A)") (class "Default")
      (node (ref "D3") (pin "1") (pinfunction "A_1") (pintype "passive"))
      (node (ref "L1") (pin "1") (pinfunction "1_1") (pintype "passive"))
      (node (ref "U2") (pin "8") (pinfunction "LX_8") (pintype "passive"))
    )
    (net (code "58") (name "Net-(D4-PadK)") (class "Default")
      (node (ref "D4") (pin "K") (pinfunction "K_K") (pintype "passive"))
      (node (ref "R8") (pin "1") (pinfunction "1_1") (pintype "passive"))
    )
    (net (code "59") (name "Net-(D5-PadK)") (class "Default")
      (node (ref "D5") (pin "K") (pinfunction "K_K") (pintype "passive"))
      (node (ref "R11") (pin "2") (pinfunction "2_2") (pintype "passive"))
    )
    (net (code "60") (name "Net-(D6-PadK)") (class "Default")
      (node (ref "D6") (pin "K") (pinfunction "K_K") (pintype "passive"))
      (node (ref "R12") (pin "2") (pinfunction "2_2") (pintype "passive"))
    )
    (net (code "61") (name "Net-(D7-PadK)") (class "Default")
      (node (ref "D7") (pin "K") (pinfunction "K_K") (pintype "passive"))
      (node (ref "R26") (pin "1") (pinfunction "1_1") (pintype "passive"))
    )
    (net (code "62") (name "Net-(IC1-V3)") (class "Default")
      (node (ref "C10") (pin "2") (pinfunction "2_2") (pintype "passive"))
      (node (ref "IC1") (pin "4") (pinfunction "V3_4") (pintype "passive"))
    )
    (net (code "63") (name "Net-(IC1-XI)") (class "Default")
      (node (ref "C12") (pin "1") (pinfunction "1_1") (pintype "passive"))
      (node (ref "IC1") (pin "7") (pinfunction "XI_7") (pintype "passive"))
      (node (ref "Y1") (pin "1") (pinfunction "1_1") (pintype "passive"))
    )
    (net (code "64") (name "Net-(IC1-XO)") (class "Default")
      (node (ref "C11") (pin "1") (pinfunction "1_1") (pintype "passive"))
      (node (ref "IC1") (pin "8") (pinfunction "XO_8") (pintype "passive"))
      (node (ref "Y1") (pin "2") (pinfunction "2_2") (pintype "passive"))
    )
    (net (code "65") (name "Net-(K1-Pad1)") (class "Default")
      (node (ref "K1") (pin "1") (pinfunction "1_1") (pintype "passive"))
      (node (ref "R27") (pin "2") (pinfunction "2_2") (pintype "passive"))
      (node (ref "R29") (pin "2") (pinfunction "2_2") (pintype "passive"))
      (node (ref "R31") (pin "1") (pinfunction "1_1") (pintype "passive"))
    )
    (net (code "66") (name "Net-(K2-Pad1)") (class "Default")
      (node (ref "K2") (pin "1") (pinfunction "1_1") (pintype "passive"))
      (node (ref "R28") (pin "2") (pinfunction "2_2") (pintype "passive"))
      (node (ref "R30") (pin "2") (pinfunction "2_2") (pintype "passive"))
      (node (ref "R32") (pin "1") (pinfunction "1_1") (pintype "passive"))
    )
    (net (code "67") (name "Net-(K3-Pad1)") (class "Default")
      (node (ref "K3") (pin "1") (pinfunction "1_1") (pintype "passive"))
      (node (ref "R31") (pin "2") (pinfunction "2_2") (pintype "passive"))
      (node (ref "R34") (pin "1") (pinfunction "1_1") (pintype "passive"))
    )
    (net (code "68") (name "Net-(K4-Pad1)") (class "Default")
      (node (ref "K4") (pin "1") (pinfunction "1_1") (pintype "passive"))
      (node (ref "R32") (pin "2") (pinfunction "2_2") (pintype "passive"))
      (node (ref "R35") (pin "1") (pinfunction "1_1") (pintype "passive"))
    )
    (net (code "69") (name "Net-(K5-Pad1)") (class "Default")
      (node (ref "K5") (pin "1") (pinfunction "1_1") (pintype "passive"))
      (node (ref "R34") (pin "2") (pinfunction "2_2") (pintype "passive"))
      (node (ref "R36") (pin "1") (pinfunction "1_1") (pintype "passive"))
    )
    (net (code "70") (name "Net-(K6-Pad1)") (class "Default")
      (node (ref "K6") (pin "1") (pinfunction "1_1") (pintype "passive"))
      (node (ref "R35") (pin "2") (pinfunction "2_2") (pintype "passive"))
      (node (ref "R37") (pin "1") (pinfunction "1_1") (pintype "passive"))
    )
    (net (code "71") (name "Net-(K7-Pad1)") (class "Default")
      (node (ref "K7") (pin "1") (pinfunction "1_1") (pintype "passive"))
      (node (ref "R36") (pin "2") (pinfunction "2_2") (pintype "passive"))
    )
    (net (code "72") (name "Net-(K8-Pad1)") (class "Default")
      (node (ref "K8") (pin "1") (pinfunction "1_1") (pintype "passive"))
      (node (ref "R37") (pin "2") (pinfunction "2_2") (pintype "passive"))
    )
    (net (code "73") (name "Net-(M1-PIO8)") (class "Default")
      (node (ref "D4") (pin "A") (pinfunction "A_A") (pintype "passive"))
      (node (ref "M1") (pin "31") (pinfunction "PIO8_31") (pintype "passive"))
    )
    (net (code "74") (name "Net-(M1-PIO11)") (class "Default")
      (node (ref "M1") (pin "34") (pinfunction "PIO11_34") (pintype "passive"))
      (node (ref "R5") (pin "1") (pinfunction "1_1") (pintype "passive"))
      (node (ref "R7") (pin "1") (pinfunction "1_1") (pintype "passive"))
    )
    (net (code "75") (name "Net-(Q1-B)") (class "Default")
      (node (ref "Q1") (pin "1") (pinfunction "B_1") (pintype "passive"))
      (node (ref "R39") (pin "2") (pinfunction "2_2") (pintype "passive"))
      (node (ref "R43") (pin "2") (pinfunction "2_2") (pintype "passive"))
    )
    (net (code "76") (name "Net-(Q1-C)") (class "Default")
      (node (ref "Q1") (pin "3") (pinfunction "C_3") (pintype "passive"))
      (node (ref "R38") (pin "2") (pinfunction "2_2") (pintype "passive"))
      (node (ref "R40") (pin "2") (pinfunction "2_2") (pintype "passive"))
      (node (ref "R41") (pin "2") (pinfunction "2_2") (pintype "passive"))
    )
    (net (code "77") (name "Net-(Q1-E)") (class "Default")
      (node (ref "D10") (pin "A") (pinfunction "A_A") (pintype "passive"))
      (node (ref "D11") (pin "A") (pinfunction "A_A") (pintype "passive"))
      (node (ref "D12") (pin "A") (pinfunction "A_A") (pintype "passive"))
      (node (ref "D13") (pin "A") (pinfunction "A_A") (pintype "passive"))
      (node (ref "D14") (pin "A") (pinfunction "A_A") (pintype "passive"))
      (node (ref "D15") (pin "A") (pinfunction "A_A") (pintype "passive"))
      (node (ref "D16") (pin "A") (pinfunction "A_A") (pintype "passive"))
      (node (ref "D17") (pin "A") (pinfunction "A_A") (pintype "passive"))
      (node (ref "D18") (pin "A") (pinfunction "A_A") (pintype "passive"))
      (node (ref "D19") (pin "A") (pinfunction "A_A") (pintype "passive"))
      (node (ref "D8") (pin "A") (pinfunction "A_A") (pintype "passive"))
      (node (ref "D9") (pin "A") (pinfunction "A_A") (pintype "passive"))
      (node (ref "Q1") (pin "2") (pinfunction "E_2") (pintype "passive"))
      (node (ref "R39") (pin "1") (pinfunction "1_1") (pintype "passive"))
    )
    (net (code "78") (name "Net-(Q2-B)") (class "Default")
      (node (ref "Q2") (pin "1") (pinfunction "B_1") (pintype "passive"))
      (node (ref "R46") (pin "2") (pinfunction "2_2") (pintype "passive"))
      (node (ref "R49") (pin "2") (pinfunction "2_2") (pintype "passive"))
    )
    (net (code "79") (name "Net-(Q2-C)") (class "Default")
      (node (ref "Q2") (pin "3") (pinfunction "C_3") (pintype "passive"))
      (node (ref "R45") (pin "2") (pinfunction "2_2") (pintype "passive"))
      (node (ref "R47") (pin "2") (pinfunction "2_2") (pintype "passive"))
      (node (ref "R48") (pin "2") (pinfunction "2_2") (pintype "passive"))
    )
    (net (code "80") (name "Net-(Q2-E)") (class "Default")
      (node (ref "D20") (pin "A") (pinfunction "A_A") (pintype "passive"))
      (node (ref "D21") (pin "A") (pinfunction "A_A") (pintype "passive"))
      (node (ref "D22") (pin "A") (pinfunction "A_A") (pintype "passive"))
      (node (ref "D23") (pin "A") (pinfunction "A_A") (pintype "passive"))
      (node (ref "D24") (pin "A") (pinfunction "A_A") (pintype "passive"))
      (node (ref "D25") (pin "A") (pinfunction "A_A") (pintype "passive"))
      (node (ref "D26") (pin "A") (pinfunction "A_A") (pintype "passive"))
      (node (ref "D27") (pin "A") (pinfunction "A_A") (pintype "passive"))
      (node (ref "D28") (pin "A") (pinfunction "A_A") (pintype "passive"))
      (node (ref "D29") (pin "A") (pinfunction "A_A") (pintype "passive"))
      (node (ref "D30") (pin "A") (pinfunction "A_A") (pintype "passive"))
      (node (ref "D31") (pin "A") (pinfunction "A_A") (pintype "passive"))
      (node (ref "Q2") (pin "2") (pinfunction "E_2") (pintype "passive"))
      (node (ref "R46") (pin "1") (pinfunction "1_1") (pintype "passive"))
    )
    (net (code "81") (name "Net-(R5-Pad2)") (class "Default")
      (node (ref "R5") (pin "2") (pinfunction "2_2") (pintype "passive"))
      (node (ref "SW1") (pin "1") (pinfunction "1_1") (pintype "passive"))
    )
    (net (code "82") (name "Net-(R22-Pad1)") (class "Default")
      (node (ref "R22") (pin "1") (pinfunction "1_1") (pintype "passive"))
      (node (ref "Stick_L1") (pin "3") (pinfunction "TOP_3") (pintype "passive"))
    )
    (net (code "83") (name "Net-(R23-Pad1)") (class "Default")
      (node (ref "R23") (pin "1") (pinfunction "1_1") (pintype "passive"))
      (node (ref "Stick_R1") (pin "3") (pinfunction "TOP_3") (pintype "passive"))
    )
    (net (code "84") (name "Net-(R24-Pad1)") (class "Default")
      (node (ref "R24") (pin "1") (pinfunction "1_1") (pintype "passive"))
      (node (ref "Stick_L1") (pin "6") (pinfunction "TOP_6") (pintype "passive"))
    )
    (net (code "85") (name "Net-(R25-Pad1)") (class "Default")
      (node (ref "R25") (pin "1") (pinfunction "1_1") (pintype "passive"))
      (node (ref "Stick_R1") (pin "6") (pinfunction "TOP_6") (pintype "passive"))
    )
    (net (code "86") (name "Net-(U1-CPOUT)") (class "Default")
      (node (ref "C5") (pin "2") (pinfunction "2_2") (pintype "passive"))
      (node (ref "U1") (pin "20") (pinfunction "CPOUT_20") (pintype "passive"))
    )
    (net (code "87") (name "Net-(U1-INT)") (class "Default")
      (node (ref "R4") (pin "1") (pinfunction "1_1") (pintype "passive"))
      (node (ref "U1") (pin "12") (pinfunction "INT_12") (pintype "passive"))
    )
    (net (code "88") (name "Net-(U1-REGOUT)") (class "Default")
      (node (ref "C6") (pin "1") (pinfunction "1_1") (pintype "passive"))
      (node (ref "U1") (pin "10") (pinfunction "REGOUT_10") (pintype "passive"))
    )
    (net (code "89") (name "Net-(U2-PROG)") (class "Default")
      (node (ref "R13") (pin "1") (pinfunction "1_1") (pintype "passive"))
      (node (ref "U2") (pin "3") (pinfunction "PROG_3") (pintype "passive"))
    )
    (net (code "90") (name "Net-(U2-VCC)") (class "Default")
      (node (ref "C1") (pin "2") (pinfunction "2_2") (pintype "passive"))
      (node (ref "R2") (pin "1") (pinfunction "1_1") (pintype "passive"))
      (node (ref "R6") (pin "1") (pinfunction "1_1") (pintype "passive"))
      (node (ref "U2") (pin "5") (pinfunction "VCC_5") (pintype "passive"))
    )
    (net (code "91") (name "Net-(U2-~{CHRG})") (class "Default")
      (node (ref "D2") (pin "K") (pinfunction "K_K") (pintype "passive"))
      (node (ref "U2") (pin "2") (pinfunction "~{CHRG}_2") (pintype "passive"))
    )
    (net (code "92") (name "Net-(U2-~{STDBY})") (class "Default")
      (node (ref "D1") (pin "K") (pinfunction "K_K") (pintype "passive"))
      (node (ref "U2") (pin "4") (pinfunction "~{STDBY}_4") (pintype "passive"))
    )
    (net (code "93") (name "Net-(U4-GPIO16)") (class "Default")
      (node (ref "R17") (pin "1") (pinfunction "1_1") (pintype "passive"))
      (node (ref "U4") (pin "5") (pinfunction "GPIO16_5") (pintype "passive"))
    )
    (net (code "94") (name "Net-(U7-BOOT0)") (class "Default")
      (node (ref "R33") (pin "1") (pinfunction "1_1") (pintype "passive"))
      (node (ref "U7") (pin "44") (pinfunction "BOOT0_44") (pintype "input"))
    )
    (net (code "95") (name "Net-(USB1-+5V)") (class "Default")
      (node (ref "F1") (pin "1") (pinfunction "1_1") (pintype "passive"))
      (node (ref "USB1") (pin "1") (pinfunction "+5V_1") (pintype "passive"))
    )
    (net (code "96") (name "VCC") (class "Default")
      (node (ref "*1") (pin "1") (pinfunction "5V_1") (pintype "passive"))
      (node (ref "C13") (pin "2") (pinfunction "2_2") (pintype "passive"))
      (node (ref "C15") (pin "2") (pinfunction "2_2") (pintype "passive"))
      (node (ref "C7") (pin "1") (pinfunction "1_1") (pintype "passive"))
      (node (ref "C8") (pin "1") (pinfunction "1_1") (pintype "passive"))
      (node (ref "D5") (pin "A") (pinfunction "A_A") (pintype "passive"))
      (node (ref "IC1") (pin "16") (pinfunction "Vcc_16") (pintype "passive"))
      (node (ref "S1") (pin "2") (pinfunction "2_2") (pintype "passive"))
      (node (ref "U5") (pin "1") (pinfunction "VIN_1") (pintype "passive"))
      (node (ref "U5") (pin "3") (pinfunction "EN_3") (pintype "passive"))
      (node (ref "U6") (pin "1") (pinfunction "VIN_1") (pintype "passive"))
      (node (ref "U6") (pin "3") (pinfunction "EN_3") (pintype "passive"))
    )
    (net (code "97") (name "unconnected-(IC1-CTS#-Pad9)") (class "Default")
      (node (ref "IC1") (pin "9") (pinfunction "CTS#_9") (pintype "passive"))
    )
    (net (code "98") (name "unconnected-(IC1-DCD#-Pad12)") (class "Default")
      (node (ref "IC1") (pin "12") (pinfunction "DCD#_12") (pintype "passive"))
    )
    (net (code "99") (name "unconnected-(IC1-DSR#-Pad10)") (class "Default")
      (node (ref "IC1") (pin "10") (pinfunction "DSR#_10") (pintype "passive"))
    )
    (net (code "100") (name "unconnected-(IC1-DTR#-Pad13)") (class "Default")
      (node (ref "IC1") (pin "13") (pinfunction "DTR#_13") (pintype "passive"))
    )
    (net (code "101") (name "unconnected-(IC1-RI#-Pad11)") (class "Default")
      (node (ref "IC1") (pin "11") (pinfunction "RI#_11") (pintype "passive"))
    )
    (net (code "102") (name "unconnected-(IC1-RS232-Pad15)") (class "Default")
      (node (ref "IC1") (pin "15") (pinfunction "RS232_15") (pintype "passive"))
    )
    (net (code "103") (name "unconnected-(IC1-RTS#-Pad14)") (class "Default")
      (node (ref "IC1") (pin "14") (pinfunction "RTS#_14") (pintype "passive"))
    )
    (net (code "104") (name "unconnected-(M1-AIO0-Pad9)") (class "Default")
      (node (ref "M1") (pin "9") (pinfunction "AIO0_9") (pintype "passive"))
    )
    (net (code "105") (name "unconnected-(M1-AIO1-Pad10)") (class "Default")
      (node (ref "M1") (pin "10") (pinfunction "AIO1_10") (pintype "passive"))
    )
    (net (code "106") (name "unconnected-(M1-CLK-Pad19)") (class "Default")
      (node (ref "M1") (pin "19") (pinfunction "CLK_19") (pintype "passive"))
    )
    (net (code "107") (name "unconnected-(M1-CSB-Pad16)") (class "Default")
      (node (ref "M1") (pin "16") (pinfunction "CSB_16") (pintype "passive"))
    )
    (net (code "108") (name "unconnected-(M1-CTS-Pad3)") (class "Default")
      (node (ref "M1") (pin "3") (pinfunction "CTS_3") (pintype "passive"))
    )
    (net (code "109") (name "unconnected-(M1-MISO-Pad18)") (class "Default")
      (node (ref "M1") (pin "18") (pinfunction "MISO_18") (pintype "passive"))
    )
    (net (code "110") (name "unconnected-(M1-MOSI-Pad17)") (class "Default")
      (node (ref "M1") (pin "17") (pinfunction "MOSI_17") (pintype "passive"))
    )
    (net (code "111") (name "unconnected-(M1-NC-Pad14)") (class "Default")
      (node (ref "M1") (pin "14") (pinfunction "NC_14") (pintype "passive"))
    )
    (net (code "112") (name "unconnected-(M1-PCM_CLK-Pad5)") (class "Default")
      (node (ref "M1") (pin "5") (pinfunction "PCM_CLK_5") (pintype "passive"))
    )
    (net (code "113") (name "unconnected-(M1-PCM_IN-Pad7)") (class "Default")
      (node (ref "M1") (pin "7") (pinfunction "PCM_IN_7") (pintype "passive"))
    )
    (net (code "114") (name "unconnected-(M1-PCM_OUT-Pad6)") (class "Default")
      (node (ref "M1") (pin "6") (pinfunction "PCM_OUT_6") (pintype "passive"))
    )
    (net (code "115") (name "unconnected-(M1-PCM_SYNC-Pad8)") (class "Default")
      (node (ref "M1") (pin "8") (pinfunction "PCM_SYNC_8") (pintype "passive"))
    )
    (net (code "116") (name "unconnected-(M1-PIO0-Pad23)") (class "Default")
      (node (ref "M1") (pin "23") (pinfunction "PIO0_23") (pintype "passive"))
    )
    (net (code "117") (name "unconnected-(M1-PIO1-Pad24)") (class "Default")
      (node (ref "M1") (pin "24") (pinfunction "PIO1_24") (pintype "passive"))
    )
    (net (code "118") (name "unconnected-(M1-PIO2-Pad25)") (class "Default")
      (node (ref "M1") (pin "25") (pinfunction "PIO2_25") (pintype "passive"))
    )
    (net (code "119") (name "unconnected-(M1-PIO3-Pad26)") (class "Default")
      (node (ref "M1") (pin "26") (pinfunction "PIO3_26") (pintype "passive"))
    )
    (net (code "120") (name "unconnected-(M1-PIO4-Pad27)") (class "Default")
      (node (ref "M1") (pin "27") (pinfunction "PIO4_27") (pintype "passive"))
    )
    (net (code "121") (name "unconnected-(M1-PIO5-Pad28)") (class "Default")
      (node (ref "M1") (pin "28") (pinfunction "PIO5_28") (pintype "passive"))
    )
    (net (code "122") (name "unconnected-(M1-PIO6-Pad29)") (class "Default")
      (node (ref "M1") (pin "29") (pinfunction "PIO6_29") (pintype "passive"))
    )
    (net (code "123") (name "unconnected-(M1-PIO7-Pad30)") (class "Default")
      (node (ref "M1") (pin "30") (pinfunction "PIO7_30") (pintype "passive"))
    )
    (net (code "124") (name "unconnected-(M1-PIO9-Pad32)") (class "Default")
      (node (ref "M1") (pin "32") (pinfunction "PIO9_32") (pintype "passive"))
    )
    (net (code "125") (name "unconnected-(M1-PIO10-Pad33)") (class "Default")
      (node (ref "M1") (pin "33") (pinfunction "PIO10_33") (pintype "passive"))
    )
    (net (code "126") (name "unconnected-(M1-RESET-Pad11)") (class "Default")
      (node (ref "M1") (pin "11") (pinfunction "RESET_11") (pintype "passive"))
    )
    (net (code "127") (name "unconnected-(M1-RT3-Pad4)") (class "Default")
      (node (ref "M1") (pin "4") (pinfunction "RT3_4") (pintype "passive"))
    )
    (net (code "128") (name "unconnected-(M1-USB_D+-Pad20)") (class "Default")
      (node (ref "M1") (pin "20") (pinfunction "USB_D+_20") (pintype "passive"))
    )
    (net (code "129") (name "unconnected-(M1-USB_D--Pad15)") (class "Default")
      (node (ref "M1") (pin "15") (pinfunction "USB_D-_15") (pintype "passive"))
    )
    (net (code "130") (name "unconnected-(S1-Pad6)") (class "Default")
      (node (ref "S1") (pin "6") (pinfunction "6_6") (pintype "passive"))
    )
    (net (code "131") (name "unconnected-(U1-AUX_CL-Pad7)") (class "Default")
      (node (ref "U1") (pin "7") (pinfunction "AUX_CL_7") (pintype "passive"))
    )
    (net (code "132") (name "unconnected-(U1-AUX_DA-Pad6)") (class "Default")
      (node (ref "U1") (pin "6") (pinfunction "AUX_DA_6") (pintype "passive"))
    )
    (net (code "133") (name "unconnected-(U1-NC-Pad2)") (class "Default")
      (node (ref "U1") (pin "2") (pinfunction "NC_2") (pintype "passive"))
    )
    (net (code "134") (name "unconnected-(U1-NC-Pad3)") (class "Default")
      (node (ref "U1") (pin "3") (pinfunction "NC_3") (pintype "passive"))
    )
    (net (code "135") (name "unconnected-(U1-NC-Pad4)") (class "Default")
      (node (ref "U1") (pin "4") (pinfunction "NC_4") (pintype "passive"))
    )
    (net (code "136") (name "unconnected-(U1-NC-Pad5)") (class "Default")
      (node (ref "U1") (pin "5") (pinfunction "NC_5") (pintype "passive"))
    )
    (net (code "137") (name "unconnected-(U1-NC-Pad14)") (class "Default")
      (node (ref "U1") (pin "14") (pinfunction "NC_14") (pintype "passive"))
    )
    (net (code "138") (name "unconnected-(U1-NC-Pad15)") (class "Default")
      (node (ref "U1") (pin "15") (pinfunction "NC_15") (pintype "passive"))
    )
    (net (code "139") (name "unconnected-(U1-NC-Pad16)") (class "Default")
      (node (ref "U1") (pin "16") (pinfunction "NC_16") (pintype "passive"))
    )
    (net (code "140") (name "unconnected-(U1-NC-Pad17)") (class "Default")
      (node (ref "U1") (pin "17") (pinfunction "NC_17") (pintype "passive"))
    )
    (net (code "141") (name "unconnected-(U1-RESV-Pad19)") (class "Default")
      (node (ref "U1") (pin "19") (pinfunction "RESV_19") (pintype "passive"))
    )
    (net (code "142") (name "unconnected-(U1-RESV-Pad21)") (class "Default")
      (node (ref "U1") (pin "21") (pinfunction "RESV_21") (pintype "passive"))
    )
    (net (code "143") (name "unconnected-(U1-RESV-Pad22)") (class "Default")
      (node (ref "U1") (pin "22") (pinfunction "RESV_22") (pintype "passive"))
    )
    (net (code "144") (name "unconnected-(U4-CH_PD-Pad3)") (class "Default")
      (node (ref "U4") (pin "3") (pinfunction "CH_PD_3") (pintype "passive"))
    )
    (net (code "145") (name "unconnected-(U4-GPIO0-Pad6)") (class "Default")
      (node (ref "U4") (pin "6") (pinfunction "GPIO0_6") (pintype "passive"))
    )
    (net (code "146") (name "unconnected-(U4-GPIO2-Pad4)") (class "Default")
      (node (ref "U4") (pin "4") (pinfunction "GPIO2_4") (pintype "passive"))
    )
    (net (code "147") (name "unconnected-(U5-ADJ{slash}BYP-Pad4)") (class "Default")
      (node (ref "U5") (pin "4") (pinfunction "ADJ/BYP_4") (pintype "passive"))
    )
    (net (code "148") (name "unconnected-(U6-ADJ{slash}BYP-Pad4)") (class "Default")
      (node (ref "U6") (pin "4") (pinfunction "ADJ/BYP_4") (pintype "passive"))
    )
    (net (code "149") (name "unconnected-(USB1-ID-Pad4)") (class "Default")
      (node (ref "USB1") (pin "4") (pinfunction "ID_4") (pintype "passive"))
    )
  )
)
